# MCU_POWER.net
KiCad netlist of a schematic drawn in Altium Designer
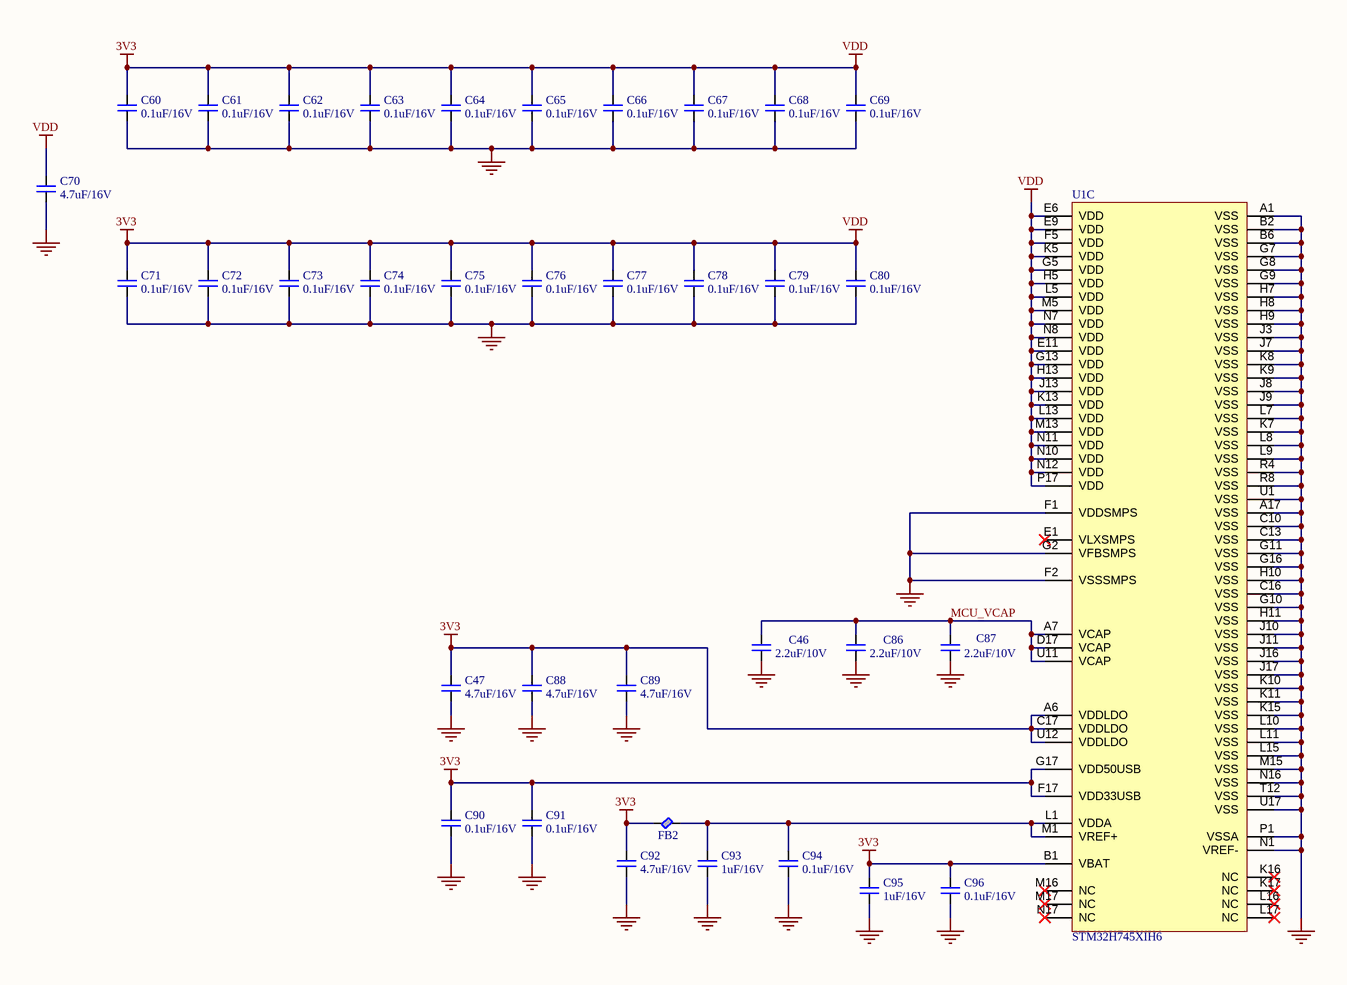
[diagram p0: MCU_POWER.SchDoc]

(export (version "E")
  (design (tool "Eeschema 10.0.6"))
  (components
    (comp (ref "C46")
      (value "2.2uF/10V")
      (footprint "CAP_C_1608X80")
      (description "CAP_Chip")
      (libsource (lib "LABLIB") (part "CAP_SMD"))
    )
    (comp (ref "C47")
      (value "4.7uF/16V")
      (footprint "CAP_C_1608X80")
      (description "CAP_Chip")
      (libsource (lib "LABLIB") (part "CAP_SMD"))
    )
    (comp (ref "C60")
      (value "0.1uF/16V")
      (footprint "CAP_C_1608X80")
      (description "CAP_Chip")
      (libsource (lib "LABLIB") (part "CAP_SMD"))
    )
    (comp (ref "C61")
      (value "0.1uF/16V")
      (footprint "CAP_C_1608X80")
      (description "CAP_Chip")
      (libsource (lib "LABLIB") (part "CAP_SMD"))
    )
    (comp (ref "C62")
      (value "0.1uF/16V")
      (footprint "CAP_C_1608X80")
      (description "CAP_Chip")
      (libsource (lib "LABLIB") (part "CAP_SMD"))
    )
    (comp (ref "C63")
      (value "0.1uF/16V")
      (footprint "CAP_C_1608X80")
      (description "CAP_Chip")
      (libsource (lib "LABLIB") (part "CAP_SMD"))
    )
    (comp (ref "C64")
      (value "0.1uF/16V")
      (footprint "CAP_C_1608X80")
      (description "CAP_Chip")
      (libsource (lib "LABLIB") (part "CAP_SMD"))
    )
    (comp (ref "C65")
      (value "0.1uF/16V")
      (footprint "CAP_C_1608X80")
      (description "CAP_Chip")
      (libsource (lib "LABLIB") (part "CAP_SMD"))
    )
    (comp (ref "C66")
      (value "0.1uF/16V")
      (footprint "CAP_C_1608X80")
      (description "CAP_Chip")
      (libsource (lib "LABLIB") (part "CAP_SMD"))
    )
    (comp (ref "C67")
      (value "0.1uF/16V")
      (footprint "CAP_C_1608X80")
      (description "CAP_Chip")
      (libsource (lib "LABLIB") (part "CAP_SMD"))
    )
    (comp (ref "C68")
      (value "0.1uF/16V")
      (footprint "CAP_C_1608X80")
      (description "CAP_Chip")
      (libsource (lib "LABLIB") (part "CAP_SMD"))
    )
    (comp (ref "C69")
      (value "0.1uF/16V")
      (footprint "CAP_C_1608X80")
      (description "CAP_Chip")
      (libsource (lib "LABLIB") (part "CAP_SMD"))
    )
    (comp (ref "C70")
      (value "4.7uF/16V")
      (footprint "CAP_C_1608X80")
      (description "CAP_Chip")
      (libsource (lib "LABLIB") (part "CAP_SMD"))
    )
    (comp (ref "C71")
      (value "0.1uF/16V")
      (footprint "CAP_C_1608X80")
      (description "CAP_Chip")
      (libsource (lib "LABLIB") (part "CAP_SMD"))
    )
    (comp (ref "C72")
      (value "0.1uF/16V")
      (footprint "CAP_C_1608X80")
      (description "CAP_Chip")
      (libsource (lib "LABLIB") (part "CAP_SMD"))
    )
    (comp (ref "C73")
      (value "0.1uF/16V")
      (footprint "CAP_C_1608X80")
      (description "CAP_Chip")
      (libsource (lib "LABLIB") (part "CAP_SMD"))
    )
    (comp (ref "C74")
      (value "0.1uF/16V")
      (footprint "CAP_C_1608X80")
      (description "CAP_Chip")
      (libsource (lib "LABLIB") (part "CAP_SMD"))
    )
    (comp (ref "C75")
      (value "0.1uF/16V")
      (footprint "CAP_C_1608X80")
      (description "CAP_Chip")
      (libsource (lib "LABLIB") (part "CAP_SMD"))
    )
    (comp (ref "C76")
      (value "0.1uF/16V")
      (footprint "CAP_C_1608X80")
      (description "CAP_Chip")
      (libsource (lib "LABLIB") (part "CAP_SMD"))
    )
    (comp (ref "C77")
      (value "0.1uF/16V")
      (footprint "CAP_C_1608X80")
      (description "CAP_Chip")
      (libsource (lib "LABLIB") (part "CAP_SMD"))
    )
    (comp (ref "C78")
      (value "0.1uF/16V")
      (footprint "CAP_C_1608X80")
      (description "CAP_Chip")
      (libsource (lib "LABLIB") (part "CAP_SMD"))
    )
    (comp (ref "C79")
      (value "0.1uF/16V")
      (footprint "CAP_C_1608X80")
      (description "CAP_Chip")
      (libsource (lib "LABLIB") (part "CAP_SMD"))
    )
    (comp (ref "C80")
      (value "0.1uF/16V")
      (footprint "CAP_C_1608X80")
      (description "CAP_Chip")
      (libsource (lib "LABLIB") (part "CAP_SMD"))
    )
    (comp (ref "C86")
      (value "2.2uF/10V")
      (footprint "CAP_C_1608X80")
      (description "CAP_Chip")
      (libsource (lib "LABLIB") (part "CAP_SMD"))
    )
    (comp (ref "C87")
      (value "2.2uF/10V")
      (footprint "CAP_C_1608X80")
      (description "CAP_Chip")
      (libsource (lib "LABLIB") (part "CAP_SMD"))
    )
    (comp (ref "C88")
      (value "4.7uF/16V")
      (footprint "CAP_C_1608X80")
      (description "CAP_Chip")
      (libsource (lib "LABLIB") (part "CAP_SMD"))
    )
    (comp (ref "C89")
      (value "4.7uF/16V")
      (footprint "CAP_C_1608X80")
      (description "CAP_Chip")
      (libsource (lib "LABLIB") (part "CAP_SMD"))
    )
    (comp (ref "C90")
      (value "0.1uF/16V")
      (footprint "CAP_C_1608X80")
      (description "CAP_Chip")
      (libsource (lib "LABLIB") (part "CAP_SMD"))
    )
    (comp (ref "C91")
      (value "0.1uF/16V")
      (footprint "CAP_C_1608X80")
      (description "CAP_Chip")
      (libsource (lib "LABLIB") (part "CAP_SMD"))
    )
    (comp (ref "C92")
      (value "4.7uF/16V")
      (footprint "CAP_C_1608X80")
      (description "CAP_Chip")
      (libsource (lib "LABLIB") (part "CAP_SMD"))
    )
    (comp (ref "C93")
      (value "1uF/16V")
      (footprint "CAP_C_1608X80")
      (description "CAP_Chip")
      (libsource (lib "LABLIB") (part "CAP_SMD"))
    )
    (comp (ref "C94")
      (value "0.1uF/16V")
      (footprint "CAP_C_1608X80")
      (description "CAP_Chip")
      (libsource (lib "LABLIB") (part "CAP_SMD"))
    )
    (comp (ref "C95")
      (value "1uF/16V")
      (footprint "CAP_C_1608X80")
      (description "CAP_Chip")
      (libsource (lib "LABLIB") (part "CAP_SMD"))
    )
    (comp (ref "C96")
      (value "0.1uF/16V")
      (footprint "CAP_C_1608X80")
      (description "CAP_Chip")
      (libsource (lib "LABLIB") (part "CAP_SMD"))
    )
    (comp (ref "FB2")
      (value "BLM18PG121SN1D")
      (footprint "IND_1608x65")
      (description "FERRITE BEAD")
      (libsource (lib "COMM_SCHLIB") (part "FB"))
    )
    (comp (ref "U1")
      (value "STM32H745XIH6")
      (footprint "BGA265C80P17X17_1400X1400X110N")
      (fields (field (name "COPYRIGHT") "Copyright (C) 2025 Ultra Librarian. All rights reserved."))
      (libsource (lib "COMM_SCHLIB") (part "STM32H745XIH6"))
    )
  )
  (nets
    (net (code "1") (name "/MCU_VCAP") (class "Default")
      (node (ref "C46") (pin "2") (pinfunction "2_2") (pintype "passive"))
      (node (ref "C86") (pin "2") (pinfunction "2_2") (pintype "passive"))
      (node (ref "C87") (pin "2") (pinfunction "2_2") (pintype "passive"))
      (node (ref "U1") (pin "A7") (pinfunction "VCAP_A7") (pintype "power_in"))
      (node (ref "U1") (pin "D17") (pinfunction "VCAP_D17") (pintype "power_in"))
      (node (ref "U1") (pin "U11") (pinfunction "VCAP_U11") (pintype "power_in"))
    )
    (net (code "2") (name "3V3") (class "Default")
      (node (ref "C47") (pin "1") (pinfunction "1_1") (pintype "passive"))
      (node (ref "C60") (pin "2") (pinfunction "2_2") (pintype "passive"))
      (node (ref "C61") (pin "2") (pinfunction "2_2") (pintype "passive"))
      (node (ref "C62") (pin "2") (pinfunction "2_2") (pintype "passive"))
      (node (ref "C63") (pin "2") (pinfunction "2_2") (pintype "passive"))
      (node (ref "C64") (pin "2") (pinfunction "2_2") (pintype "passive"))
      (node (ref "C65") (pin "2") (pinfunction "2_2") (pintype "passive"))
      (node (ref "C66") (pin "2") (pinfunction "2_2") (pintype "passive"))
      (node (ref "C67") (pin "2") (pinfunction "2_2") (pintype "passive"))
      (node (ref "C68") (pin "2") (pinfunction "2_2") (pintype "passive"))
      (node (ref "C69") (pin "2") (pinfunction "2_2") (pintype "passive"))
      (node (ref "C70") (pin "1") (pinfunction "1_1") (pintype "passive"))
      (node (ref "C71") (pin "2") (pinfunction "2_2") (pintype "passive"))
      (node (ref "C72") (pin "2") (pinfunction "2_2") (pintype "passive"))
      (node (ref "C73") (pin "2") (pinfunction "2_2") (pintype "passive"))
      (node (ref "C74") (pin "2") (pinfunction "2_2") (pintype "passive"))
      (node (ref "C75") (pin "2") (pinfunction "2_2") (pintype "passive"))
      (node (ref "C76") (pin "2") (pinfunction "2_2") (pintype "passive"))
      (node (ref "C77") (pin "2") (pinfunction "2_2") (pintype "passive"))
      (node (ref "C78") (pin "2") (pinfunction "2_2") (pintype "passive"))
      (node (ref "C79") (pin "2") (pinfunction "2_2") (pintype "passive"))
      (node (ref "C80") (pin "2") (pinfunction "2_2") (pintype "passive"))
      (node (ref "C88") (pin "1") (pinfunction "1_1") (pintype "passive"))
      (node (ref "C89") (pin "1") (pinfunction "1_1") (pintype "passive"))
      (node (ref "C90") (pin "2") (pinfunction "2_2") (pintype "passive"))
      (node (ref "C91") (pin "2") (pinfunction "2_2") (pintype "passive"))
      (node (ref "C92") (pin "1") (pinfunction "1_1") (pintype "passive"))
      (node (ref "C95") (pin "2") (pinfunction "2_2") (pintype "passive"))
      (node (ref "C96") (pin "2") (pinfunction "2_2") (pintype "passive"))
      (node (ref "FB2") (pin "1") (pinfunction "1_1") (pintype "passive"))
      (node (ref "U1") (pin "A6") (pinfunction "VDDLDO_A6") (pintype "power_in"))
      (node (ref "U1") (pin "B1") (pinfunction "VBAT_B1") (pintype "power_in"))
      (node (ref "U1") (pin "C17") (pinfunction "VDDLDO_C17") (pintype "power_in"))
      (node (ref "U1") (pin "E11") (pinfunction "VDD_E11") (pintype "power_in"))
      (node (ref "U1") (pin "E6") (pinfunction "VDD_E6") (pintype "power_in"))
      (node (ref "U1") (pin "E9") (pinfunction "VDD_E9") (pintype "power_in"))
      (node (ref "U1") (pin "F17") (pinfunction "VDD33USB_F17") (pintype "power_in"))
      (node (ref "U1") (pin "F5") (pinfunction "VDD_F5") (pintype "power_in"))
      (node (ref "U1") (pin "G13") (pinfunction "VDD_G13") (pintype "power_in"))
      (node (ref "U1") (pin "G17") (pinfunction "VDD50USB_G17") (pintype "power_in"))
      (node (ref "U1") (pin "G5") (pinfunction "VDD_G5") (pintype "power_in"))
      (node (ref "U1") (pin "H13") (pinfunction "VDD_H13") (pintype "power_in"))
      (node (ref "U1") (pin "H5") (pinfunction "VDD_H5") (pintype "power_in"))
      (node (ref "U1") (pin "J13") (pinfunction "VDD_J13") (pintype "power_in"))
      (node (ref "U1") (pin "K13") (pinfunction "VDD_K13") (pintype "power_in"))
      (node (ref "U1") (pin "K5") (pinfunction "VDD_K5") (pintype "power_in"))
      (node (ref "U1") (pin "L13") (pinfunction "VDD_L13") (pintype "power_in"))
      (node (ref "U1") (pin "L5") (pinfunction "VDD_L5") (pintype "power_in"))
      (node (ref "U1") (pin "M13") (pinfunction "VDD_M13") (pintype "power_in"))
      (node (ref "U1") (pin "M5") (pinfunction "VDD_M5") (pintype "power_in"))
      (node (ref "U1") (pin "N10") (pinfunction "VDD_N10") (pintype "power_in"))
      (node (ref "U1") (pin "N11") (pinfunction "VDD_N11") (pintype "power_in"))
      (node (ref "U1") (pin "N12") (pinfunction "VDD_N12") (pintype "power_in"))
      (node (ref "U1") (pin "N7") (pinfunction "VDD_N7") (pintype "power_in"))
      (node (ref "U1") (pin "N8") (pinfunction "VDD_N8") (pintype "power_in"))
      (node (ref "U1") (pin "P17") (pinfunction "VDD_P17") (pintype "power_in"))
      (node (ref "U1") (pin "U12") (pinfunction "VDDLDO_U12") (pintype "power_in"))
    )
    (net (code "3") (name "GND") (class "Default")
      (node (ref "C46") (pin "1") (pinfunction "1_1") (pintype "passive"))
      (node (ref "C47") (pin "2") (pinfunction "2_2") (pintype "passive"))
      (node (ref "C60") (pin "1") (pinfunction "1_1") (pintype "passive"))
      (node (ref "C61") (pin "1") (pinfunction "1_1") (pintype "passive"))
      (node (ref "C62") (pin "1") (pinfunction "1_1") (pintype "passive"))
      (node (ref "C63") (pin "1") (pinfunction "1_1") (pintype "passive"))
      (node (ref "C64") (pin "1") (pinfunction "1_1") (pintype "passive"))
      (node (ref "C65") (pin "1") (pinfunction "1_1") (pintype "passive"))
      (node (ref "C66") (pin "1") (pinfunction "1_1") (pintype "passive"))
      (node (ref "C67") (pin "1") (pinfunction "1_1") (pintype "passive"))
      (node (ref "C68") (pin "1") (pinfunction "1_1") (pintype "passive"))
      (node (ref "C69") (pin "1") (pinfunction "1_1") (pintype "passive"))
      (node (ref "C70") (pin "2") (pinfunction "2_2") (pintype "passive"))
      (node (ref "C71") (pin "1") (pinfunction "1_1") (pintype "passive"))
      (node (ref "C72") (pin "1") (pinfunction "1_1") (pintype "passive"))
      (node (ref "C73") (pin "1") (pinfunction "1_1") (pintype "passive"))
      (node (ref "C74") (pin "1") (pinfunction "1_1") (pintype "passive"))
      (node (ref "C75") (pin "1") (pinfunction "1_1") (pintype "passive"))
      (node (ref "C76") (pin "1") (pinfunction "1_1") (pintype "passive"))
      (node (ref "C77") (pin "1") (pinfunction "1_1") (pintype "passive"))
      (node (ref "C78") (pin "1") (pinfunction "1_1") (pintype "passive"))
      (node (ref "C79") (pin "1") (pinfunction "1_1") (pintype "passive"))
      (node (ref "C80") (pin "1") (pinfunction "1_1") (pintype "passive"))
      (node (ref "C86") (pin "1") (pinfunction "1_1") (pintype "passive"))
      (node (ref "C87") (pin "1") (pinfunction "1_1") (pintype "passive"))
      (node (ref "C88") (pin "2") (pinfunction "2_2") (pintype "passive"))
      (node (ref "C89") (pin "2") (pinfunction "2_2") (pintype "passive"))
      (node (ref "C90") (pin "1") (pinfunction "1_1") (pintype "passive"))
      (node (ref "C91") (pin "1") (pinfunction "1_1") (pintype "passive"))
      (node (ref "C92") (pin "2") (pinfunction "2_2") (pintype "passive"))
      (node (ref "C93") (pin "1") (pinfunction "1_1") (pintype "passive"))
      (node (ref "C94") (pin "1") (pinfunction "1_1") (pintype "passive"))
      (node (ref "C95") (pin "1") (pinfunction "1_1") (pintype "passive"))
      (node (ref "C96") (pin "1") (pinfunction "1_1") (pintype "passive"))
      (node (ref "U1") (pin "A1") (pinfunction "VSS_A1") (pintype "power_in"))
      (node (ref "U1") (pin "A17") (pinfunction "VSS_A17") (pintype "power_in"))
      (node (ref "U1") (pin "B2") (pinfunction "VSS_B2") (pintype "power_in"))
      (node (ref "U1") (pin "B6") (pinfunction "VSS_B6") (pintype "power_in"))
      (node (ref "U1") (pin "C10") (pinfunction "VSS_C10") (pintype "power_in"))
      (node (ref "U1") (pin "C13") (pinfunction "VSS_C13") (pintype "power_in"))
      (node (ref "U1") (pin "C16") (pinfunction "VSS_C16") (pintype "power_in"))
      (node (ref "U1") (pin "F1") (pinfunction "VDDSMPS_F1") (pintype "power_in"))
      (node (ref "U1") (pin "F2") (pinfunction "VSSSMPS_F2") (pintype "power_in"))
      (node (ref "U1") (pin "G10") (pinfunction "VSS_G10") (pintype "power_in"))
      (node (ref "U1") (pin "G11") (pinfunction "VSS_G11") (pintype "power_in"))
      (node (ref "U1") (pin "G16") (pinfunction "VSS_G16") (pintype "power_in"))
      (node (ref "U1") (pin "G2") (pinfunction "VFBSMPS_G2") (pintype "power_in"))
      (node (ref "U1") (pin "G7") (pinfunction "VSS_G7") (pintype "power_in"))
      (node (ref "U1") (pin "G8") (pinfunction "VSS_G8") (pintype "power_in"))
      (node (ref "U1") (pin "G9") (pinfunction "VSS_G9") (pintype "power_in"))
      (node (ref "U1") (pin "H10") (pinfunction "VSS_H10") (pintype "power_in"))
      (node (ref "U1") (pin "H11") (pinfunction "VSS_H11") (pintype "power_in"))
      (node (ref "U1") (pin "H7") (pinfunction "VSS_H7") (pintype "power_in"))
      (node (ref "U1") (pin "H8") (pinfunction "VSS_H8") (pintype "power_in"))
      (node (ref "U1") (pin "H9") (pinfunction "VSS_H9") (pintype "power_in"))
      (node (ref "U1") (pin "J10") (pinfunction "VSS_J10") (pintype "power_in"))
      (node (ref "U1") (pin "J11") (pinfunction "VSS_J11") (pintype "power_in"))
      (node (ref "U1") (pin "J16") (pinfunction "VSS_J16") (pintype "power_in"))
      (node (ref "U1") (pin "J17") (pinfunction "VSS_J17") (pintype "power_in"))
      (node (ref "U1") (pin "J3") (pinfunction "VSS_J3") (pintype "power_in"))
      (node (ref "U1") (pin "J7") (pinfunction "VSS_J7") (pintype "power_in"))
      (node (ref "U1") (pin "J8") (pinfunction "VSS_J8") (pintype "power_in"))
      (node (ref "U1") (pin "J9") (pinfunction "VSS_J9") (pintype "power_in"))
      (node (ref "U1") (pin "K10") (pinfunction "VSS_K10") (pintype "power_in"))
      (node (ref "U1") (pin "K11") (pinfunction "VSS_K11") (pintype "power_in"))
      (node (ref "U1") (pin "K15") (pinfunction "VSS_K15") (pintype "power_in"))
      (node (ref "U1") (pin "K7") (pinfunction "VSS_K7") (pintype "power_in"))
      (node (ref "U1") (pin "K8") (pinfunction "VSS_K8") (pintype "power_in"))
      (node (ref "U1") (pin "K9") (pinfunction "VSS_K9") (pintype "power_in"))
      (node (ref "U1") (pin "L10") (pinfunction "VSS_L10") (pintype "power_in"))
      (node (ref "U1") (pin "L11") (pinfunction "VSS_L11") (pintype "power_in"))
      (node (ref "U1") (pin "L15") (pinfunction "VSS_L15") (pintype "power_in"))
      (node (ref "U1") (pin "L7") (pinfunction "VSS_L7") (pintype "power_in"))
      (node (ref "U1") (pin "L8") (pinfunction "VSS_L8") (pintype "power_in"))
      (node (ref "U1") (pin "L9") (pinfunction "VSS_L9") (pintype "power_in"))
      (node (ref "U1") (pin "M15") (pinfunction "VSS_M15") (pintype "power_in"))
      (node (ref "U1") (pin "N1") (pinfunction "VREF-_N1") (pintype "power_in"))
      (node (ref "U1") (pin "N16") (pinfunction "VSS_N16") (pintype "power_in"))
      (node (ref "U1") (pin "P1") (pinfunction "VSSA_P1") (pintype "power_in"))
      (node (ref "U1") (pin "R4") (pinfunction "VSS_R4") (pintype "power_in"))
      (node (ref "U1") (pin "R8") (pinfunction "VSS_R8") (pintype "power_in"))
      (node (ref "U1") (pin "T12") (pinfunction "VSS_T12") (pintype "power_in"))
      (node (ref "U1") (pin "U1") (pinfunction "VSS_U1") (pintype "power_in"))
      (node (ref "U1") (pin "U17") (pinfunction "VSS_U17") (pintype "power_in"))
    )
    (net (code "4") (name "Net-(U1C-VDDA)") (class "Default")
      (node (ref "C93") (pin "2") (pinfunction "2_2") (pintype "passive"))
      (node (ref "C94") (pin "2") (pinfunction "2_2") (pintype "passive"))
      (node (ref "FB2") (pin "2") (pinfunction "2_2") (pintype "passive"))
      (node (ref "U1") (pin "L1") (pinfunction "VDDA_L1") (pintype "power_in"))
      (node (ref "U1") (pin "M1") (pinfunction "VREF+_M1") (pintype "power_in"))
    )
    (net (code "5") (name "unconnected-(U1C-NC-PadK16)") (class "Default")
      (node (ref "U1") (pin "K16") (pinfunction "NC_K16") (pintype "passive+no_connect"))
    )
    (net (code "6") (name "unconnected-(U1C-NC-PadK17)") (class "Default")
      (node (ref "U1") (pin "K17") (pinfunction "NC_K17") (pintype "passive+no_connect"))
    )
    (net (code "7") (name "unconnected-(U1C-NC-PadL16)") (class "Default")
      (node (ref "U1") (pin "L16") (pinfunction "NC_L16") (pintype "passive+no_connect"))
    )
    (net (code "8") (name "unconnected-(U1C-NC-PadL17)") (class "Default")
      (node (ref "U1") (pin "L17") (pinfunction "NC_L17") (pintype "passive+no_connect"))
    )
    (net (code "9") (name "unconnected-(U1C-NC-PadM16)") (class "Default")
      (node (ref "U1") (pin "M16") (pinfunction "NC_M16") (pintype "passive+no_connect"))
    )
    (net (code "10") (name "unconnected-(U1C-NC-PadM17)") (class "Default")
      (node (ref "U1") (pin "M17") (pinfunction "NC_M17") (pintype "passive+no_connect"))
    )
    (net (code "11") (name "unconnected-(U1C-NC-PadN17)") (class "Default")
      (node (ref "U1") (pin "N17") (pinfunction "NC_N17") (pintype "passive+no_connect"))
    )
    (net (code "12") (name "unconnected-(U1C-VLXSMPS-PadE1)") (class "Default")
      (node (ref "U1") (pin "E1") (pinfunction "VLXSMPS_E1") (pintype "power_in+no_connect"))
    )
  )
)
